# Arduino__Connectors.net
KiCad netlist of a schematic drawn in Altium Designer
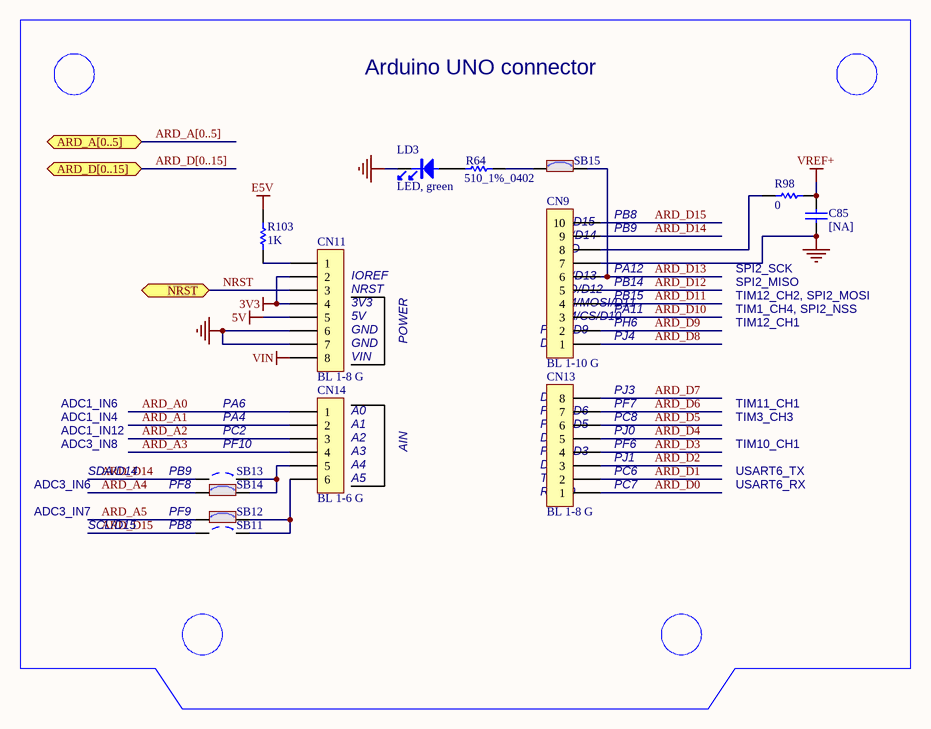
[diagram p0: Arduino_ Connectors.SchDoc]

(export (version "E")
  (design (tool "Eeschema 10.0.6"))
  (components
    (comp (ref "C85")
      (value "[NA]")
      (footprint "0402C")
      (description "Capacitor,NA,0402")
      (libsource (lib "MCD_TOOLS") (part "Cap_NA_0402"))
    )
    (comp (ref "CN9")
      (value "BL 1-10 G")
      (footprint "HDR_1X10_2R54_W")
      (description "Header, 10-Pin, Single row, female, THT, 2.54")
      (libsource (lib "MCD_TOOLS_CONNECTOR") (part "Header 10X1_Female_THT"))
    )
    (comp (ref "CN11")
      (value "BL 1-8 G")
      (footprint "HDR_1X8_2R54_W")
      (description "Header, 8-Pins, Single row, female, THT, 2.54")
      (libsource (lib "") (part "Header 8X1_Female_THT_1"))
    )
    (comp (ref "CN13")
      (value "BL 1-8 G")
      (footprint "HDR_1X8_2R54_W")
      (description "Header, 8-Pins, Single row, female, THT, 2.54")
      (libsource (lib "MCD_TOOLS_CONNECTOR") (part "Header 8X1_Female_THT"))
    )
    (comp (ref "CN14")
      (value "BL 1-6 G")
      (footprint "HDR_1X6_2R54_W")
      (description "Header, 6-Pins, Single row, female THT, 2.54")
      (libsource (lib "MCD_TOOLS_CONNECTOR") (part "Header 6X1_Female_THT"))
    )
    (comp (ref "LD3")
      (value "LED, green")
      (footprint "0603D")
      (description "LED,green,0603,19-213SYGC/S530-E2/TR8,everlight")
      (libsource (lib "MCD_TOOLS") (part "LED_green"))
    )
    (comp (ref "R64")
      (value "510_1%_0402")
      (footprint "0402R")
      (description "Resistor,510,0402,1%,YAGEO")
      (libsource (lib "MCD_TOOLS") (part "Res_510_1%_0402"))
    )
    (comp (ref "R98")
      (value "0")
      (footprint "0402R")
      (description "Resistor,0,0402,5%,YAGEO")
      (libsource (lib "MCD_TOOLS") (part "Res_0_5%_0402"))
    )
    (comp (ref "R103")
      (value "1K")
      (footprint "0402R")
      (description "Resistor,1K,0402,1%,YAGEO")
      (libsource (lib "MCD_TOOLS_RESISTOR") (part "Res_1K_1%_0402"))
    )
    (comp (ref "SB11")
      (value "Solder Bridge OFF")
      (footprint "JP2_SMD")
      (libsource (lib "MCD_TOOLS") (part "SB_OFF"))
    )
    (comp (ref "SB12")
      (value "Solder Bridge ON")
      (footprint "JP2_SMD")
      (libsource (lib "MCD_TOOLS") (part "SB_ON"))
    )
    (comp (ref "SB13")
      (value "Solder Bridge OFF")
      (footprint "JP2_SMD")
      (libsource (lib "MCD_TOOLS") (part "SB_OFF"))
    )
    (comp (ref "SB14")
      (value "Solder Bridge ON")
      (footprint "JP2_SMD")
      (libsource (lib "MCD_TOOLS") (part "SB_ON"))
    )
    (comp (ref "SB15")
      (value "Solder Bridge ON")
      (footprint "JP2_SMD")
      (libsource (lib "MCD_TOOLS") (part "SB_ON"))
    )
  )
  (nets
    (net (code "1") (name "/ARD_A0") (class "Default")
      (node (ref "CN14") (pin "1") (pinfunction "1_1") (pintype "passive"))
    )
    (net (code "2") (name "/ARD_A1") (class "Default")
      (node (ref "CN14") (pin "2") (pinfunction "2_2") (pintype "passive"))
    )
    (net (code "3") (name "/ARD_A2") (class "Default")
      (node (ref "CN14") (pin "3") (pinfunction "3_3") (pintype "passive"))
    )
    (net (code "4") (name "/ARD_A3") (class "Default")
      (node (ref "CN14") (pin "4") (pinfunction "4_4") (pintype "passive"))
    )
    (net (code "5") (name "/ARD_A4") (class "Default")
      (node (ref "SB14") (pin "1") (pinfunction "1_1") (pintype "passive"))
    )
    (net (code "6") (name "/ARD_A5") (class "Default")
      (node (ref "SB12") (pin "1") (pinfunction "1_1") (pintype "passive"))
    )
    (net (code "8") (name "/ARD_D0") (class "Default")
      (node (ref "CN13") (pin "1") (pinfunction "1_1") (pintype "passive"))
    )
    (net (code "9") (name "/ARD_D1") (class "Default")
      (node (ref "CN13") (pin "2") (pinfunction "2_2") (pintype "passive"))
    )
    (net (code "10") (name "/ARD_D2") (class "Default")
      (node (ref "CN13") (pin "3") (pinfunction "3_3") (pintype "passive"))
    )
    (net (code "11") (name "/ARD_D3") (class "Default")
      (node (ref "CN13") (pin "4") (pinfunction "4_4") (pintype "passive"))
    )
    (net (code "12") (name "/ARD_D4") (class "Default")
      (node (ref "CN13") (pin "5") (pinfunction "5_5") (pintype "passive"))
    )
    (net (code "13") (name "/ARD_D5") (class "Default")
      (node (ref "CN13") (pin "6") (pinfunction "6_6") (pintype "passive"))
    )
    (net (code "14") (name "/ARD_D6") (class "Default")
      (node (ref "CN13") (pin "7") (pinfunction "7_7") (pintype "passive"))
    )
    (net (code "15") (name "/ARD_D7") (class "Default")
      (node (ref "CN13") (pin "8") (pinfunction "8_8") (pintype "passive"))
    )
    (net (code "16") (name "/ARD_D8") (class "Default")
      (node (ref "CN9") (pin "1") (pinfunction "1_1") (pintype "passive"))
    )
    (net (code "17") (name "/ARD_D9") (class "Default")
      (node (ref "CN9") (pin "2") (pinfunction "2_2") (pintype "passive"))
    )
    (net (code "18") (name "/ARD_D10") (class "Default")
      (node (ref "CN9") (pin "3") (pinfunction "3_3") (pintype "passive"))
    )
    (net (code "19") (name "/ARD_D11") (class "Default")
      (node (ref "CN9") (pin "4") (pinfunction "4_4") (pintype "passive"))
    )
    (net (code "20") (name "/ARD_D12") (class "Default")
      (node (ref "CN9") (pin "5") (pinfunction "5_5") (pintype "passive"))
    )
    (net (code "21") (name "/ARD_D13") (class "Default")
      (node (ref "CN9") (pin "6") (pinfunction "6_6") (pintype "passive"))
      (node (ref "SB15") (pin "2") (pinfunction "2_2") (pintype "passive"))
    )
    (net (code "22") (name "/ARD_D14") (class "Default")
      (node (ref "CN9") (pin "9") (pinfunction "9_9") (pintype "passive"))
      (node (ref "SB13") (pin "1") (pinfunction "1_1") (pintype "passive"))
    )
    (net (code "23") (name "/ARD_D15") (class "Default")
      (node (ref "CN9") (pin "10") (pinfunction "10_10") (pintype "passive"))
      (node (ref "SB11") (pin "1") (pinfunction "1_1") (pintype "passive"))
    )
    (net (code "25") (name "/NRST") (class "Default")
      (node (ref "CN11") (pin "3") (pinfunction "3_3") (pintype "passive"))
    )
    (net (code "26") (name "3V3") (class "Default")
      (node (ref "CN11") (pin "2") (pinfunction "2_2") (pintype "passive"))
      (node (ref "CN11") (pin "4") (pinfunction "4_4") (pintype "passive"))
    )
    (net (code "27") (name "5V") (class "Default")
      (node (ref "CN11") (pin "5") (pinfunction "5_5") (pintype "passive"))
    )
    (net (code "28") (name "E5V") (class "Default")
      (node (ref "R103") (pin "2") (pinfunction "2_2") (pintype "passive"))
    )
    (net (code "29") (name "GND") (class "Default")
      (node (ref "C85") (pin "1") (pinfunction "1_1") (pintype "passive"))
      (node (ref "CN11") (pin "6") (pinfunction "6_6") (pintype "passive"))
      (node (ref "CN11") (pin "7") (pinfunction "7_7") (pintype "passive"))
      (node (ref "CN9") (pin "7") (pinfunction "7_7") (pintype "passive"))
      (node (ref "LD3") (pin "2") (pintype "passive"))
    )
    (net (code "30") (name "Net-(CN9-Pad8)") (class "Default")
      (node (ref "CN9") (pin "8") (pinfunction "8_8") (pintype "passive"))
      (node (ref "R98") (pin "1") (pinfunction "1_1") (pintype "passive"))
    )
    (net (code "31") (name "Net-(CN11-Pad1)") (class "Default")
      (node (ref "CN11") (pin "1") (pinfunction "1_1") (pintype "passive"))
      (node (ref "R103") (pin "1") (pinfunction "1_1") (pintype "passive"))
    )
    (net (code "32") (name "Net-(CN14-Pad5)") (class "Default")
      (node (ref "CN14") (pin "5") (pinfunction "5_5") (pintype "passive"))
      (node (ref "SB13") (pin "2") (pinfunction "2_2") (pintype "passive"))
      (node (ref "SB14") (pin "2") (pinfunction "2_2") (pintype "passive"))
    )
    (net (code "33") (name "Net-(CN14-Pad6)") (class "Default")
      (node (ref "CN14") (pin "6") (pinfunction "6_6") (pintype "passive"))
      (node (ref "SB11") (pin "2") (pinfunction "2_2") (pintype "passive"))
      (node (ref "SB12") (pin "2") (pinfunction "2_2") (pintype "passive"))
    )
    (net (code "34") (name "Net-(LD3-Pad1)") (class "Default")
      (node (ref "LD3") (pin "1") (pintype "passive"))
      (node (ref "R64") (pin "1") (pinfunction "1_1") (pintype "passive"))
    )
    (net (code "35") (name "Net-(R64-Pad2)") (class "Default")
      (node (ref "R64") (pin "2") (pinfunction "2_2") (pintype "passive"))
      (node (ref "SB15") (pin "1") (pinfunction "1_1") (pintype "passive"))
    )
    (net (code "36") (name "VIN") (class "Default")
      (node (ref "CN11") (pin "8") (pinfunction "8_8") (pintype "passive"))
    )
    (net (code "37") (name "VREF+") (class "Default")
      (node (ref "C85") (pin "2") (pinfunction "2_2") (pintype "passive"))
      (node (ref "R98") (pin "2") (pinfunction "2_2") (pintype "passive"))
    )
  )
)
